# currentBaseBoard_v4.net
KiCad netlist of a schematic drawn in EAGLE
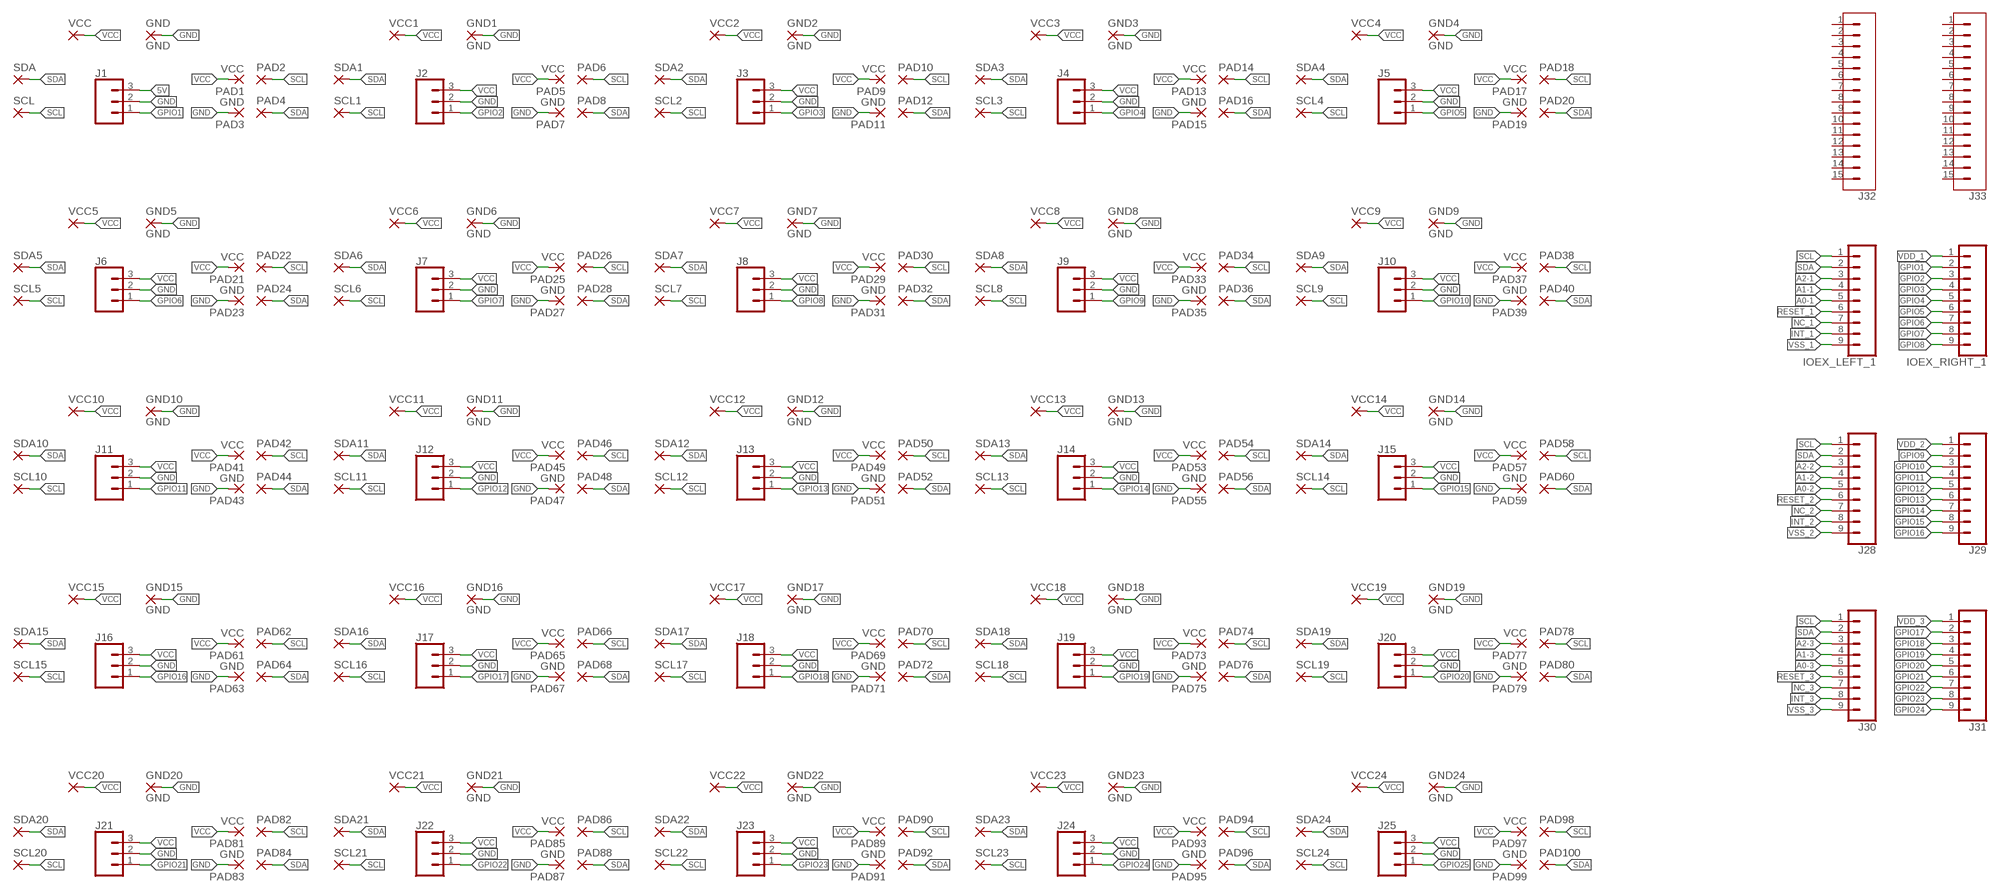
[diagram p0: schematic, sheet 1]

(export (version "E")
  (design (tool "Eeschema 10.0.6"))
  (components
    (comp (ref "GND")
      (value "GND")
      (footprint "eagle-import:2,15_1,0")
      (libsource (lib "eagle-import") (part "2,15/1,0"))
    )
    (comp (ref "GND1")
      (value "GND")
      (footprint "eagle-import:2,15_1,0")
      (libsource (lib "eagle-import") (part "2,15/1,0"))
    )
    (comp (ref "GND2")
      (value "GND")
      (footprint "eagle-import:2,15_1,0")
      (libsource (lib "eagle-import") (part "2,15/1,0"))
    )
    (comp (ref "GND3")
      (value "GND")
      (footprint "eagle-import:2,15_1,0")
      (libsource (lib "eagle-import") (part "2,15/1,0"))
    )
    (comp (ref "GND4")
      (value "GND")
      (footprint "eagle-import:2,15_1,0")
      (libsource (lib "eagle-import") (part "2,15/1,0"))
    )
    (comp (ref "GND5")
      (value "GND")
      (footprint "eagle-import:2,15_1,0")
      (libsource (lib "eagle-import") (part "2,15/1,0"))
    )
    (comp (ref "GND6")
      (value "GND")
      (footprint "eagle-import:2,15_1,0")
      (libsource (lib "eagle-import") (part "2,15/1,0"))
    )
    (comp (ref "GND7")
      (value "GND")
      (footprint "eagle-import:2,15_1,0")
      (libsource (lib "eagle-import") (part "2,15/1,0"))
    )
    (comp (ref "GND8")
      (value "GND")
      (footprint "eagle-import:2,15_1,0")
      (libsource (lib "eagle-import") (part "2,15/1,0"))
    )
    (comp (ref "GND9")
      (value "GND")
      (footprint "eagle-import:2,15_1,0")
      (libsource (lib "eagle-import") (part "2,15/1,0"))
    )
    (comp (ref "GND10")
      (value "GND")
      (footprint "eagle-import:2,15_1,0")
      (libsource (lib "eagle-import") (part "2,15/1,0"))
    )
    (comp (ref "GND11")
      (value "GND")
      (footprint "eagle-import:2,15_1,0")
      (libsource (lib "eagle-import") (part "2,15/1,0"))
    )
    (comp (ref "GND12")
      (value "GND")
      (footprint "eagle-import:2,15_1,0")
      (libsource (lib "eagle-import") (part "2,15/1,0"))
    )
    (comp (ref "GND13")
      (value "GND")
      (footprint "eagle-import:2,15_1,0")
      (libsource (lib "eagle-import") (part "2,15/1,0"))
    )
    (comp (ref "GND14")
      (value "GND")
      (footprint "eagle-import:2,15_1,0")
      (libsource (lib "eagle-import") (part "2,15/1,0"))
    )
    (comp (ref "GND15")
      (value "GND")
      (footprint "eagle-import:2,15_1,0")
      (libsource (lib "eagle-import") (part "2,15/1,0"))
    )
    (comp (ref "GND16")
      (value "GND")
      (footprint "eagle-import:2,15_1,0")
      (libsource (lib "eagle-import") (part "2,15/1,0"))
    )
    (comp (ref "GND17")
      (value "GND")
      (footprint "eagle-import:2,15_1,0")
      (libsource (lib "eagle-import") (part "2,15/1,0"))
    )
    (comp (ref "GND18")
      (value "GND")
      (footprint "eagle-import:2,15_1,0")
      (libsource (lib "eagle-import") (part "2,15/1,0"))
    )
    (comp (ref "GND19")
      (value "GND")
      (footprint "eagle-import:2,15_1,0")
      (libsource (lib "eagle-import") (part "2,15/1,0"))
    )
    (comp (ref "GND20")
      (value "GND")
      (footprint "eagle-import:2,15_1,0")
      (libsource (lib "eagle-import") (part "2,15/1,0"))
    )
    (comp (ref "GND21")
      (value "GND")
      (footprint "eagle-import:2,15_1,0")
      (libsource (lib "eagle-import") (part "2,15/1,0"))
    )
    (comp (ref "GND22")
      (value "GND")
      (footprint "eagle-import:2,15_1,0")
      (libsource (lib "eagle-import") (part "2,15/1,0"))
    )
    (comp (ref "GND23")
      (value "GND")
      (footprint "eagle-import:2,15_1,0")
      (libsource (lib "eagle-import") (part "2,15/1,0"))
    )
    (comp (ref "GND24")
      (value "GND")
      (footprint "eagle-import:2,15_1,0")
      (libsource (lib "eagle-import") (part "2,15/1,0"))
    )
    (comp (ref "IOEX_LEFT_1")
      (value "CONN_09")
      (footprint "eagle-import:1X09")
      (libsource (lib "eagle-import") (part "CONN_09"))
    )
    (comp (ref "IOEX_RIGHT_1")
      (value "CONN_09")
      (footprint "eagle-import:1X09")
      (libsource (lib "eagle-import") (part "CONN_09"))
    )
    (comp (ref "J1")
      (value "CONN_03")
      (footprint "eagle-import:1X03")
      (libsource (lib "eagle-import") (part "CONN_03"))
    )
    (comp (ref "J2")
      (value "CONN_03")
      (footprint "eagle-import:1X03")
      (libsource (lib "eagle-import") (part "CONN_03"))
    )
    (comp (ref "J3")
      (value "CONN_03")
      (footprint "eagle-import:1X03")
      (libsource (lib "eagle-import") (part "CONN_03"))
    )
    (comp (ref "J4")
      (value "CONN_03")
      (footprint "eagle-import:1X03")
      (libsource (lib "eagle-import") (part "CONN_03"))
    )
    (comp (ref "J5")
      (value "CONN_03")
      (footprint "eagle-import:1X03")
      (libsource (lib "eagle-import") (part "CONN_03"))
    )
    (comp (ref "J6")
      (value "CONN_03")
      (footprint "eagle-import:1X03")
      (libsource (lib "eagle-import") (part "CONN_03"))
    )
    (comp (ref "J7")
      (value "CONN_03")
      (footprint "eagle-import:1X03")
      (libsource (lib "eagle-import") (part "CONN_03"))
    )
    (comp (ref "J8")
      (value "CONN_03")
      (footprint "eagle-import:1X03")
      (libsource (lib "eagle-import") (part "CONN_03"))
    )
    (comp (ref "J9")
      (value "CONN_03")
      (footprint "eagle-import:1X03")
      (libsource (lib "eagle-import") (part "CONN_03"))
    )
    (comp (ref "J10")
      (value "CONN_03")
      (footprint "eagle-import:1X03")
      (libsource (lib "eagle-import") (part "CONN_03"))
    )
    (comp (ref "J11")
      (value "CONN_03")
      (footprint "eagle-import:1X03")
      (libsource (lib "eagle-import") (part "CONN_03"))
    )
    (comp (ref "J12")
      (value "CONN_03")
      (footprint "eagle-import:1X03")
      (libsource (lib "eagle-import") (part "CONN_03"))
    )
    (comp (ref "J13")
      (value "CONN_03")
      (footprint "eagle-import:1X03")
      (libsource (lib "eagle-import") (part "CONN_03"))
    )
    (comp (ref "J14")
      (value "CONN_03")
      (footprint "eagle-import:1X03")
      (libsource (lib "eagle-import") (part "CONN_03"))
    )
    (comp (ref "J15")
      (value "CONN_03")
      (footprint "eagle-import:1X03")
      (libsource (lib "eagle-import") (part "CONN_03"))
    )
    (comp (ref "J16")
      (value "CONN_03")
      (footprint "eagle-import:1X03")
      (libsource (lib "eagle-import") (part "CONN_03"))
    )
    (comp (ref "J17")
      (value "CONN_03")
      (footprint "eagle-import:1X03")
      (libsource (lib "eagle-import") (part "CONN_03"))
    )
    (comp (ref "J18")
      (value "CONN_03")
      (footprint "eagle-import:1X03")
      (libsource (lib "eagle-import") (part "CONN_03"))
    )
    (comp (ref "J19")
      (value "CONN_03")
      (footprint "eagle-import:1X03")
      (libsource (lib "eagle-import") (part "CONN_03"))
    )
    (comp (ref "J20")
      (value "CONN_03")
      (footprint "eagle-import:1X03")
      (libsource (lib "eagle-import") (part "CONN_03"))
    )
    (comp (ref "J21")
      (value "CONN_03")
      (footprint "eagle-import:1X03")
      (libsource (lib "eagle-import") (part "CONN_03"))
    )
    (comp (ref "J22")
      (value "CONN_03")
      (footprint "eagle-import:1X03")
      (libsource (lib "eagle-import") (part "CONN_03"))
    )
    (comp (ref "J23")
      (value "CONN_03")
      (footprint "eagle-import:1X03")
      (libsource (lib "eagle-import") (part "CONN_03"))
    )
    (comp (ref "J24")
      (value "CONN_03")
      (footprint "eagle-import:1X03")
      (libsource (lib "eagle-import") (part "CONN_03"))
    )
    (comp (ref "J25")
      (value "CONN_03")
      (footprint "eagle-import:1X03")
      (libsource (lib "eagle-import") (part "CONN_03"))
    )
    (comp (ref "J28")
      (value "CONN_09")
      (footprint "eagle-import:1X09")
      (libsource (lib "eagle-import") (part "CONN_09"))
    )
    (comp (ref "J29")
      (value "CONN_09")
      (footprint "eagle-import:1X09")
      (libsource (lib "eagle-import") (part "CONN_09"))
    )
    (comp (ref "J30")
      (value "CONN_09")
      (footprint "eagle-import:1X09")
      (libsource (lib "eagle-import") (part "CONN_09"))
    )
    (comp (ref "J31")
      (value "CONN_09")
      (footprint "eagle-import:1X09")
      (libsource (lib "eagle-import") (part "CONN_09"))
    )
    (comp (ref "J32")
      (value "CONN_06SMD_MALE")
      (footprint "eagle-import:1X15_SMD_MALE")
      (libsource (lib "eagle-import") (part "CONN_06SMD_MALE"))
    )
    (comp (ref "J33")
      (value "CONN_06SMD_MALE")
      (footprint "eagle-import:1X15_SMD_MALE")
      (libsource (lib "eagle-import") (part "CONN_06SMD_MALE"))
    )
    (comp (ref "PAD1")
      (value "VCC")
      (footprint "eagle-import:2,15_1,0")
      (libsource (lib "eagle-import") (part "2,15/1,0"))
    )
    (comp (ref "PAD2")
      (value "2,15/1,0")
      (footprint "eagle-import:2,15_1,0")
      (libsource (lib "eagle-import") (part "2,15/1,0"))
    )
    (comp (ref "PAD3")
      (value "GND")
      (footprint "eagle-import:2,15_1,0")
      (libsource (lib "eagle-import") (part "2,15/1,0"))
    )
    (comp (ref "PAD4")
      (value "2,15/1,0")
      (footprint "eagle-import:2,15_1,0")
      (libsource (lib "eagle-import") (part "2,15/1,0"))
    )
    (comp (ref "PAD5")
      (value "VCC")
      (footprint "eagle-import:2,15_1,0")
      (libsource (lib "eagle-import") (part "2,15/1,0"))
    )
    (comp (ref "PAD6")
      (value "2,15/1,0")
      (footprint "eagle-import:2,15_1,0")
      (libsource (lib "eagle-import") (part "2,15/1,0"))
    )
    (comp (ref "PAD7")
      (value "GND")
      (footprint "eagle-import:2,15_1,0")
      (libsource (lib "eagle-import") (part "2,15/1,0"))
    )
    (comp (ref "PAD8")
      (value "2,15/1,0")
      (footprint "eagle-import:2,15_1,0")
      (libsource (lib "eagle-import") (part "2,15/1,0"))
    )
    (comp (ref "PAD9")
      (value "VCC")
      (footprint "eagle-import:2,15_1,0")
      (libsource (lib "eagle-import") (part "2,15/1,0"))
    )
    (comp (ref "PAD10")
      (value "2,15/1,0")
      (footprint "eagle-import:2,15_1,0")
      (libsource (lib "eagle-import") (part "2,15/1,0"))
    )
    (comp (ref "PAD11")
      (value "GND")
      (footprint "eagle-import:2,15_1,0")
      (libsource (lib "eagle-import") (part "2,15/1,0"))
    )
    (comp (ref "PAD12")
      (value "2,15/1,0")
      (footprint "eagle-import:2,15_1,0")
      (libsource (lib "eagle-import") (part "2,15/1,0"))
    )
    (comp (ref "PAD13")
      (value "VCC")
      (footprint "eagle-import:2,15_1,0")
      (libsource (lib "eagle-import") (part "2,15/1,0"))
    )
    (comp (ref "PAD14")
      (value "2,15/1,0")
      (footprint "eagle-import:2,15_1,0")
      (libsource (lib "eagle-import") (part "2,15/1,0"))
    )
    (comp (ref "PAD15")
      (value "GND")
      (footprint "eagle-import:2,15_1,0")
      (libsource (lib "eagle-import") (part "2,15/1,0"))
    )
    (comp (ref "PAD16")
      (value "2,15/1,0")
      (footprint "eagle-import:2,15_1,0")
      (libsource (lib "eagle-import") (part "2,15/1,0"))
    )
    (comp (ref "PAD17")
      (value "VCC")
      (footprint "eagle-import:2,15_1,0")
      (libsource (lib "eagle-import") (part "2,15/1,0"))
    )
    (comp (ref "PAD18")
      (value "2,15/1,0")
      (footprint "eagle-import:2,15_1,0")
      (libsource (lib "eagle-import") (part "2,15/1,0"))
    )
    (comp (ref "PAD19")
      (value "GND")
      (footprint "eagle-import:2,15_1,0")
      (libsource (lib "eagle-import") (part "2,15/1,0"))
    )
    (comp (ref "PAD20")
      (value "2,15/1,0")
      (footprint "eagle-import:2,15_1,0")
      (libsource (lib "eagle-import") (part "2,15/1,0"))
    )
    (comp (ref "PAD21")
      (value "VCC")
      (footprint "eagle-import:2,15_1,0")
      (libsource (lib "eagle-import") (part "2,15/1,0"))
    )
    (comp (ref "PAD22")
      (value "2,15/1,0")
      (footprint "eagle-import:2,15_1,0")
      (libsource (lib "eagle-import") (part "2,15/1,0"))
    )
    (comp (ref "PAD23")
      (value "GND")
      (footprint "eagle-import:2,15_1,0")
      (libsource (lib "eagle-import") (part "2,15/1,0"))
    )
    (comp (ref "PAD24")
      (value "2,15/1,0")
      (footprint "eagle-import:2,15_1,0")
      (libsource (lib "eagle-import") (part "2,15/1,0"))
    )
    (comp (ref "PAD25")
      (value "VCC")
      (footprint "eagle-import:2,15_1,0")
      (libsource (lib "eagle-import") (part "2,15/1,0"))
    )
    (comp (ref "PAD26")
      (value "2,15/1,0")
      (footprint "eagle-import:2,15_1,0")
      (libsource (lib "eagle-import") (part "2,15/1,0"))
    )
    (comp (ref "PAD27")
      (value "GND")
      (footprint "eagle-import:2,15_1,0")
      (libsource (lib "eagle-import") (part "2,15/1,0"))
    )
    (comp (ref "PAD28")
      (value "2,15/1,0")
      (footprint "eagle-import:2,15_1,0")
      (libsource (lib "eagle-import") (part "2,15/1,0"))
    )
    (comp (ref "PAD29")
      (value "VCC")
      (footprint "eagle-import:2,15_1,0")
      (libsource (lib "eagle-import") (part "2,15/1,0"))
    )
    (comp (ref "PAD30")
      (value "2,15/1,0")
      (footprint "eagle-import:2,15_1,0")
      (libsource (lib "eagle-import") (part "2,15/1,0"))
    )
    (comp (ref "PAD31")
      (value "GND")
      (footprint "eagle-import:2,15_1,0")
      (libsource (lib "eagle-import") (part "2,15/1,0"))
    )
    (comp (ref "PAD32")
      (value "2,15/1,0")
      (footprint "eagle-import:2,15_1,0")
      (libsource (lib "eagle-import") (part "2,15/1,0"))
    )
    (comp (ref "PAD33")
      (value "VCC")
      (footprint "eagle-import:2,15_1,0")
      (libsource (lib "eagle-import") (part "2,15/1,0"))
    )
    (comp (ref "PAD34")
      (value "2,15/1,0")
      (footprint "eagle-import:2,15_1,0")
      (libsource (lib "eagle-import") (part "2,15/1,0"))
    )
    (comp (ref "PAD35")
      (value "GND")
      (footprint "eagle-import:2,15_1,0")
      (libsource (lib "eagle-import") (part "2,15/1,0"))
    )
    (comp (ref "PAD36")
      (value "2,15/1,0")
      (footprint "eagle-import:2,15_1,0")
      (libsource (lib "eagle-import") (part "2,15/1,0"))
    )
    (comp (ref "PAD37")
      (value "VCC")
      (footprint "eagle-import:2,15_1,0")
      (libsource (lib "eagle-import") (part "2,15/1,0"))
    )
    (comp (ref "PAD38")
      (value "2,15/1,0")
      (footprint "eagle-import:2,15_1,0")
      (libsource (lib "eagle-import") (part "2,15/1,0"))
    )
    (comp (ref "PAD39")
      (value "GND")
      (footprint "eagle-import:2,15_1,0")
      (libsource (lib "eagle-import") (part "2,15/1,0"))
    )
    (comp (ref "PAD40")
      (value "2,15/1,0")
      (footprint "eagle-import:2,15_1,0")
      (libsource (lib "eagle-import") (part "2,15/1,0"))
    )
    (comp (ref "PAD41")
      (value "VCC")
      (footprint "eagle-import:2,15_1,0")
      (libsource (lib "eagle-import") (part "2,15/1,0"))
    )
    (comp (ref "PAD42")
      (value "2,15/1,0")
      (footprint "eagle-import:2,15_1,0")
      (libsource (lib "eagle-import") (part "2,15/1,0"))
    )
    (comp (ref "PAD43")
      (value "GND")
      (footprint "eagle-import:2,15_1,0")
      (libsource (lib "eagle-import") (part "2,15/1,0"))
    )
    (comp (ref "PAD44")
      (value "2,15/1,0")
      (footprint "eagle-import:2,15_1,0")
      (libsource (lib "eagle-import") (part "2,15/1,0"))
    )
    (comp (ref "PAD45")
      (value "VCC")
      (footprint "eagle-import:2,15_1,0")
      (libsource (lib "eagle-import") (part "2,15/1,0"))
    )
    (comp (ref "PAD46")
      (value "2,15/1,0")
      (footprint "eagle-import:2,15_1,0")
      (libsource (lib "eagle-import") (part "2,15/1,0"))
    )
    (comp (ref "PAD47")
      (value "GND")
      (footprint "eagle-import:2,15_1,0")
      (libsource (lib "eagle-import") (part "2,15/1,0"))
    )
    (comp (ref "PAD48")
      (value "2,15/1,0")
      (footprint "eagle-import:2,15_1,0")
      (libsource (lib "eagle-import") (part "2,15/1,0"))
    )
    (comp (ref "PAD49")
      (value "VCC")
      (footprint "eagle-import:2,15_1,0")
      (libsource (lib "eagle-import") (part "2,15/1,0"))
    )
    (comp (ref "PAD50")
      (value "2,15/1,0")
      (footprint "eagle-import:2,15_1,0")
      (libsource (lib "eagle-import") (part "2,15/1,0"))
    )
    (comp (ref "PAD51")
      (value "GND")
      (footprint "eagle-import:2,15_1,0")
      (libsource (lib "eagle-import") (part "2,15/1,0"))
    )
    (comp (ref "PAD52")
      (value "2,15/1,0")
      (footprint "eagle-import:2,15_1,0")
      (libsource (lib "eagle-import") (part "2,15/1,0"))
    )
    (comp (ref "PAD53")
      (value "VCC")
      (footprint "eagle-import:2,15_1,0")
      (libsource (lib "eagle-import") (part "2,15/1,0"))
    )
    (comp (ref "PAD54")
      (value "2,15/1,0")
      (footprint "eagle-import:2,15_1,0")
      (libsource (lib "eagle-import") (part "2,15/1,0"))
    )
    (comp (ref "PAD55")
      (value "GND")
      (footprint "eagle-import:2,15_1,0")
      (libsource (lib "eagle-import") (part "2,15/1,0"))
    )
    (comp (ref "PAD56")
      (value "2,15/1,0")
      (footprint "eagle-import:2,15_1,0")
      (libsource (lib "eagle-import") (part "2,15/1,0"))
    )
    (comp (ref "PAD57")
      (value "VCC")
      (footprint "eagle-import:2,15_1,0")
      (libsource (lib "eagle-import") (part "2,15/1,0"))
    )
    (comp (ref "PAD58")
      (value "2,15/1,0")
      (footprint "eagle-import:2,15_1,0")
      (libsource (lib "eagle-import") (part "2,15/1,0"))
    )
    (comp (ref "PAD59")
      (value "GND")
      (footprint "eagle-import:2,15_1,0")
      (libsource (lib "eagle-import") (part "2,15/1,0"))
    )
    (comp (ref "PAD60")
      (value "2,15/1,0")
      (footprint "eagle-import:2,15_1,0")
      (libsource (lib "eagle-import") (part "2,15/1,0"))
    )
    (comp (ref "PAD61")
      (value "VCC")
      (footprint "eagle-import:2,15_1,0")
      (libsource (lib "eagle-import") (part "2,15/1,0"))
    )
    (comp (ref "PAD62")
      (value "2,15/1,0")
      (footprint "eagle-import:2,15_1,0")
      (libsource (lib "eagle-import") (part "2,15/1,0"))
    )
    (comp (ref "PAD63")
      (value "GND")
      (footprint "eagle-import:2,15_1,0")
      (libsource (lib "eagle-import") (part "2,15/1,0"))
    )
    (comp (ref "PAD64")
      (value "2,15/1,0")
      (footprint "eagle-import:2,15_1,0")
      (libsource (lib "eagle-import") (part "2,15/1,0"))
    )
    (comp (ref "PAD65")
      (value "VCC")
      (footprint "eagle-import:2,15_1,0")
      (libsource (lib "eagle-import") (part "2,15/1,0"))
    )
    (comp (ref "PAD66")
      (value "2,15/1,0")
      (footprint "eagle-import:2,15_1,0")
      (libsource (lib "eagle-import") (part "2,15/1,0"))
    )
    (comp (ref "PAD67")
      (value "GND")
      (footprint "eagle-import:2,15_1,0")
      (libsource (lib "eagle-import") (part "2,15/1,0"))
    )
    (comp (ref "PAD68")
      (value "2,15/1,0")
      (footprint "eagle-import:2,15_1,0")
      (libsource (lib "eagle-import") (part "2,15/1,0"))
    )
    (comp (ref "PAD69")
      (value "VCC")
      (footprint "eagle-import:2,15_1,0")
      (libsource (lib "eagle-import") (part "2,15/1,0"))
    )
    (comp (ref "PAD70")
      (value "2,15/1,0")
      (footprint "eagle-import:2,15_1,0")
      (libsource (lib "eagle-import") (part "2,15/1,0"))
    )
    (comp (ref "PAD71")
      (value "GND")
      (footprint "eagle-import:2,15_1,0")
      (libsource (lib "eagle-import") (part "2,15/1,0"))
    )
    (comp (ref "PAD72")
      (value "2,15/1,0")
      (footprint "eagle-import:2,15_1,0")
      (libsource (lib "eagle-import") (part "2,15/1,0"))
    )
    (comp (ref "PAD73")
      (value "VCC")
      (footprint "eagle-import:2,15_1,0")
      (libsource (lib "eagle-import") (part "2,15/1,0"))
    )
    (comp (ref "PAD74")
      (value "2,15/1,0")
      (footprint "eagle-import:2,15_1,0")
      (libsource (lib "eagle-import") (part "2,15/1,0"))
    )
    (comp (ref "PAD75")
      (value "GND")
      (footprint "eagle-import:2,15_1,0")
      (libsource (lib "eagle-import") (part "2,15/1,0"))
    )
    (comp (ref "PAD76")
      (value "2,15/1,0")
      (footprint "eagle-import:2,15_1,0")
      (libsource (lib "eagle-import") (part "2,15/1,0"))
    )
    (comp (ref "PAD77")
      (value "VCC")
      (footprint "eagle-import:2,15_1,0")
      (libsource (lib "eagle-import") (part "2,15/1,0"))
    )
    (comp (ref "PAD78")
      (value "2,15/1,0")
      (footprint "eagle-import:2,15_1,0")
      (libsource (lib "eagle-import") (part "2,15/1,0"))
    )
    (comp (ref "PAD79")
      (value "GND")
      (footprint "eagle-import:2,15_1,0")
      (libsource (lib "eagle-import") (part "2,15/1,0"))
    )
    (comp (ref "PAD80")
      (value "2,15/1,0")
      (footprint "eagle-import:2,15_1,0")
      (libsource (lib "eagle-import") (part "2,15/1,0"))
    )
    (comp (ref "PAD81")
      (value "VCC")
      (footprint "eagle-import:2,15_1,0")
      (libsource (lib "eagle-import") (part "2,15/1,0"))
    )
    (comp (ref "PAD82")
      (value "2,15/1,0")
      (footprint "eagle-import:2,15_1,0")
      (libsource (lib "eagle-import") (part "2,15/1,0"))
    )
    (comp (ref "PAD83")
      (value "GND")
      (footprint "eagle-import:2,15_1,0")
      (libsource (lib "eagle-import") (part "2,15/1,0"))
    )
    (comp (ref "PAD84")
      (value "2,15/1,0")
      (footprint "eagle-import:2,15_1,0")
      (libsource (lib "eagle-import") (part "2,15/1,0"))
    )
    (comp (ref "PAD85")
      (value "VCC")
      (footprint "eagle-import:2,15_1,0")
      (libsource (lib "eagle-import") (part "2,15/1,0"))
    )
    (comp (ref "PAD86")
      (value "2,15/1,0")
      (footprint "eagle-import:2,15_1,0")
      (libsource (lib "eagle-import") (part "2,15/1,0"))
    )
    (comp (ref "PAD87")
      (value "GND")
      (footprint "eagle-import:2,15_1,0")
      (libsource (lib "eagle-import") (part "2,15/1,0"))
    )
    (comp (ref "PAD88")
      (value "2,15/1,0")
      (footprint "eagle-import:2,15_1,0")
      (libsource (lib "eagle-import") (part "2,15/1,0"))
    )
    (comp (ref "PAD89")
      (value "VCC")
      (footprint "eagle-import:2,15_1,0")
      (libsource (lib "eagle-import") (part "2,15/1,0"))
    )
    (comp (ref "PAD90")
      (value "2,15/1,0")
      (footprint "eagle-import:2,15_1,0")
      (libsource (lib "eagle-import") (part "2,15/1,0"))
    )
    (comp (ref "PAD91")
      (value "GND")
      (footprint "eagle-import:2,15_1,0")
      (libsource (lib "eagle-import") (part "2,15/1,0"))
    )
    (comp (ref "PAD92")
      (value "2,15/1,0")
      (footprint "eagle-import:2,15_1,0")
      (libsource (lib "eagle-import") (part "2,15/1,0"))
    )
    (comp (ref "PAD93")
      (value "VCC")
      (footprint "eagle-import:2,15_1,0")
      (libsource (lib "eagle-import") (part "2,15/1,0"))
    )
    (comp (ref "PAD94")
      (value "2,15/1,0")
      (footprint "eagle-import:2,15_1,0")
      (libsource (lib "eagle-import") (part "2,15/1,0"))
    )
    (comp (ref "PAD95")
      (value "GND")
      (footprint "eagle-import:2,15_1,0")
      (libsource (lib "eagle-import") (part "2,15/1,0"))
    )
    (comp (ref "PAD96")
      (value "2,15/1,0")
      (footprint "eagle-import:2,15_1,0")
      (libsource (lib "eagle-import") (part "2,15/1,0"))
    )
    (comp (ref "PAD97")
      (value "VCC")
      (footprint "eagle-import:2,15_1,0")
      (libsource (lib "eagle-import") (part "2,15/1,0"))
    )
    (comp (ref "PAD98")
      (value "2,15/1,0")
      (footprint "eagle-import:2,15_1,0")
      (libsource (lib "eagle-import") (part "2,15/1,0"))
    )
    (comp (ref "PAD99")
      (value "GND")
      (footprint "eagle-import:2,15_1,0")
      (libsource (lib "eagle-import") (part "2,15/1,0"))
    )
    (comp (ref "PAD100")
      (value "2,15/1,0")
      (footprint "eagle-import:2,15_1,0")
      (libsource (lib "eagle-import") (part "2,15/1,0"))
    )
    (comp (ref "SCL")
      (value "2,15/1,0")
      (footprint "eagle-import:2,15_1,0")
      (libsource (lib "eagle-import") (part "2,15/1,0"))
    )
    (comp (ref "SCL1")
      (value "2,15/1,0")
      (footprint "eagle-import:2,15_1,0")
      (libsource (lib "eagle-import") (part "2,15/1,0"))
    )
    (comp (ref "SCL2")
      (value "2,15/1,0")
      (footprint "eagle-import:2,15_1,0")
      (libsource (lib "eagle-import") (part "2,15/1,0"))
    )
    (comp (ref "SCL3")
      (value "2,15/1,0")
      (footprint "eagle-import:2,15_1,0")
      (libsource (lib "eagle-import") (part "2,15/1,0"))
    )
    (comp (ref "SCL4")
      (value "2,15/1,0")
      (footprint "eagle-import:2,15_1,0")
      (libsource (lib "eagle-import") (part "2,15/1,0"))
    )
    (comp (ref "SCL5")
      (value "2,15/1,0")
      (footprint "eagle-import:2,15_1,0")
      (libsource (lib "eagle-import") (part "2,15/1,0"))
    )
    (comp (ref "SCL6")
      (value "2,15/1,0")
      (footprint "eagle-import:2,15_1,0")
      (libsource (lib "eagle-import") (part "2,15/1,0"))
    )
    (comp (ref "SCL7")
      (value "2,15/1,0")
      (footprint "eagle-import:2,15_1,0")
      (libsource (lib "eagle-import") (part "2,15/1,0"))
    )
    (comp (ref "SCL8")
      (value "2,15/1,0")
      (footprint "eagle-import:2,15_1,0")
      (libsource (lib "eagle-import") (part "2,15/1,0"))
    )
    (comp (ref "SCL9")
      (value "2,15/1,0")
      (footprint "eagle-import:2,15_1,0")
      (libsource (lib "eagle-import") (part "2,15/1,0"))
    )
    (comp (ref "SCL10")
      (value "2,15/1,0")
      (footprint "eagle-import:2,15_1,0")
      (libsource (lib "eagle-import") (part "2,15/1,0"))
    )
    (comp (ref "SCL11")
      (value "2,15/1,0")
      (footprint "eagle-import:2,15_1,0")
      (libsource (lib "eagle-import") (part "2,15/1,0"))
    )
    (comp (ref "SCL12")
      (value "2,15/1,0")
      (footprint "eagle-import:2,15_1,0")
      (libsource (lib "eagle-import") (part "2,15/1,0"))
    )
    (comp (ref "SCL13")
      (value "2,15/1,0")
      (footprint "eagle-import:2,15_1,0")
      (libsource (lib "eagle-import") (part "2,15/1,0"))
    )
    (comp (ref "SCL14")
      (value "2,15/1,0")
      (footprint "eagle-import:2,15_1,0")
      (libsource (lib "eagle-import") (part "2,15/1,0"))
    )
    (comp (ref "SCL15")
      (value "2,15/1,0")
      (footprint "eagle-import:2,15_1,0")
      (libsource (lib "eagle-import") (part "2,15/1,0"))
    )
    (comp (ref "SCL16")
      (value "2,15/1,0")
      (footprint "eagle-import:2,15_1,0")
      (libsource (lib "eagle-import") (part "2,15/1,0"))
    )
    (comp (ref "SCL17")
      (value "2,15/1,0")
      (footprint "eagle-import:2,15_1,0")
      (libsource (lib "eagle-import") (part "2,15/1,0"))
    )
    (comp (ref "SCL18")
      (value "2,15/1,0")
      (footprint "eagle-import:2,15_1,0")
      (libsource (lib "eagle-import") (part "2,15/1,0"))
    )
    (comp (ref "SCL19")
      (value "2,15/1,0")
      (footprint "eagle-import:2,15_1,0")
      (libsource (lib "eagle-import") (part "2,15/1,0"))
    )
    (comp (ref "SCL20")
      (value "2,15/1,0")
      (footprint "eagle-import:2,15_1,0")
      (libsource (lib "eagle-import") (part "2,15/1,0"))
    )
    (comp (ref "SCL21")
      (value "2,15/1,0")
      (footprint "eagle-import:2,15_1,0")
      (libsource (lib "eagle-import") (part "2,15/1,0"))
    )
    (comp (ref "SCL22")
      (value "2,15/1,0")
      (footprint "eagle-import:2,15_1,0")
      (libsource (lib "eagle-import") (part "2,15/1,0"))
    )
    (comp (ref "SCL23")
      (value "2,15/1,0")
      (footprint "eagle-import:2,15_1,0")
      (libsource (lib "eagle-import") (part "2,15/1,0"))
    )
    (comp (ref "SCL24")
      (value "2,15/1,0")
      (footprint "eagle-import:2,15_1,0")
      (libsource (lib "eagle-import") (part "2,15/1,0"))
    )
    (comp (ref "SDA")
      (value "2,15/1,0")
      (footprint "eagle-import:2,15_1,0")
      (libsource (lib "eagle-import") (part "2,15/1,0"))
    )
    (comp (ref "SDA1")
      (value "2,15/1,0")
      (footprint "eagle-import:2,15_1,0")
      (libsource (lib "eagle-import") (part "2,15/1,0"))
    )
    (comp (ref "SDA2")
      (value "2,15/1,0")
      (footprint "eagle-import:2,15_1,0")
      (libsource (lib "eagle-import") (part "2,15/1,0"))
    )
    (comp (ref "SDA3")
      (value "2,15/1,0")
      (footprint "eagle-import:2,15_1,0")
      (libsource (lib "eagle-import") (part "2,15/1,0"))
    )
    (comp (ref "SDA4")
      (value "2,15/1,0")
      (footprint "eagle-import:2,15_1,0")
      (libsource (lib "eagle-import") (part "2,15/1,0"))
    )
    (comp (ref "SDA5")
      (value "2,15/1,0")
      (footprint "eagle-import:2,15_1,0")
      (libsource (lib "eagle-import") (part "2,15/1,0"))
    )
    (comp (ref "SDA6")
      (value "2,15/1,0")
      (footprint "eagle-import:2,15_1,0")
      (libsource (lib "eagle-import") (part "2,15/1,0"))
    )
    (comp (ref "SDA7")
      (value "2,15/1,0")
      (footprint "eagle-import:2,15_1,0")
      (libsource (lib "eagle-import") (part "2,15/1,0"))
    )
    (comp (ref "SDA8")
      (value "2,15/1,0")
      (footprint "eagle-import:2,15_1,0")
      (libsource (lib "eagle-import") (part "2,15/1,0"))
    )
    (comp (ref "SDA9")
      (value "2,15/1,0")
      (footprint "eagle-import:2,15_1,0")
      (libsource (lib "eagle-import") (part "2,15/1,0"))
    )
    (comp (ref "SDA10")
      (value "2,15/1,0")
      (footprint "eagle-import:2,15_1,0")
      (libsource (lib "eagle-import") (part "2,15/1,0"))
    )
    (comp (ref "SDA11")
      (value "2,15/1,0")
      (footprint "eagle-import:2,15_1,0")
      (libsource (lib "eagle-import") (part "2,15/1,0"))
    )
    (comp (ref "SDA12")
      (value "2,15/1,0")
      (footprint "eagle-import:2,15_1,0")
      (libsource (lib "eagle-import") (part "2,15/1,0"))
    )
    (comp (ref "SDA13")
      (value "2,15/1,0")
      (footprint "eagle-import:2,15_1,0")
      (libsource (lib "eagle-import") (part "2,15/1,0"))
    )
    (comp (ref "SDA14")
      (value "2,15/1,0")
      (footprint "eagle-import:2,15_1,0")
      (libsource (lib "eagle-import") (part "2,15/1,0"))
    )
    (comp (ref "SDA15")
      (value "2,15/1,0")
      (footprint "eagle-import:2,15_1,0")
      (libsource (lib "eagle-import") (part "2,15/1,0"))
    )
    (comp (ref "SDA16")
      (value "2,15/1,0")
      (footprint "eagle-import:2,15_1,0")
      (libsource (lib "eagle-import") (part "2,15/1,0"))
    )
    (comp (ref "SDA17")
      (value "2,15/1,0")
      (footprint "eagle-import:2,15_1,0")
      (libsource (lib "eagle-import") (part "2,15/1,0"))
    )
    (comp (ref "SDA18")
      (value "2,15/1,0")
      (footprint "eagle-import:2,15_1,0")
      (libsource (lib "eagle-import") (part "2,15/1,0"))
    )
    (comp (ref "SDA19")
      (value "2,15/1,0")
      (footprint "eagle-import:2,15_1,0")
      (libsource (lib "eagle-import") (part "2,15/1,0"))
    )
    (comp (ref "SDA20")
      (value "2,15/1,0")
      (footprint "eagle-import:2,15_1,0")
      (libsource (lib "eagle-import") (part "2,15/1,0"))
    )
    (comp (ref "SDA21")
      (value "2,15/1,0")
      (footprint "eagle-import:2,15_1,0")
      (libsource (lib "eagle-import") (part "2,15/1,0"))
    )
    (comp (ref "SDA22")
      (value "2,15/1,0")
      (footprint "eagle-import:2,15_1,0")
      (libsource (lib "eagle-import") (part "2,15/1,0"))
    )
    (comp (ref "SDA23")
      (value "2,15/1,0")
      (footprint "eagle-import:2,15_1,0")
      (libsource (lib "eagle-import") (part "2,15/1,0"))
    )
    (comp (ref "SDA24")
      (value "2,15/1,0")
      (footprint "eagle-import:2,15_1,0")
      (libsource (lib "eagle-import") (part "2,15/1,0"))
    )
    (comp (ref "VCC")
      (value "2,15/1,0")
      (footprint "eagle-import:2,15_1,0")
      (libsource (lib "eagle-import") (part "2,15/1,0"))
    )
    (comp (ref "VCC1")
      (value "2,15/1,0")
      (footprint "eagle-import:2,15_1,0")
      (libsource (lib "eagle-import") (part "2,15/1,0"))
    )
    (comp (ref "VCC2")
      (value "2,15/1,0")
      (footprint "eagle-import:2,15_1,0")
      (libsource (lib "eagle-import") (part "2,15/1,0"))
    )
    (comp (ref "VCC3")
      (value "2,15/1,0")
      (footprint "eagle-import:2,15_1,0")
      (libsource (lib "eagle-import") (part "2,15/1,0"))
    )
    (comp (ref "VCC4")
      (value "2,15/1,0")
      (footprint "eagle-import:2,15_1,0")
      (libsource (lib "eagle-import") (part "2,15/1,0"))
    )
    (comp (ref "VCC5")
      (value "2,15/1,0")
      (footprint "eagle-import:2,15_1,0")
      (libsource (lib "eagle-import") (part "2,15/1,0"))
    )
    (comp (ref "VCC6")
      (value "2,15/1,0")
      (footprint "eagle-import:2,15_1,0")
      (libsource (lib "eagle-import") (part "2,15/1,0"))
    )
    (comp (ref "VCC7")
      (value "2,15/1,0")
      (footprint "eagle-import:2,15_1,0")
      (libsource (lib "eagle-import") (part "2,15/1,0"))
    )
    (comp (ref "VCC8")
      (value "2,15/1,0")
      (footprint "eagle-import:2,15_1,0")
      (libsource (lib "eagle-import") (part "2,15/1,0"))
    )
    (comp (ref "VCC9")
      (value "2,15/1,0")
      (footprint "eagle-import:2,15_1,0")
      (libsource (lib "eagle-import") (part "2,15/1,0"))
    )
    (comp (ref "VCC10")
      (value "2,15/1,0")
      (footprint "eagle-import:2,15_1,0")
      (libsource (lib "eagle-import") (part "2,15/1,0"))
    )
    (comp (ref "VCC11")
      (value "2,15/1,0")
      (footprint "eagle-import:2,15_1,0")
      (libsource (lib "eagle-import") (part "2,15/1,0"))
    )
    (comp (ref "VCC12")
      (value "2,15/1,0")
      (footprint "eagle-import:2,15_1,0")
      (libsource (lib "eagle-import") (part "2,15/1,0"))
    )
    (comp (ref "VCC13")
      (value "2,15/1,0")
      (footprint "eagle-import:2,15_1,0")
      (libsource (lib "eagle-import") (part "2,15/1,0"))
    )
    (comp (ref "VCC14")
      (value "2,15/1,0")
      (footprint "eagle-import:2,15_1,0")
      (libsource (lib "eagle-import") (part "2,15/1,0"))
    )
    (comp (ref "VCC15")
      (value "2,15/1,0")
      (footprint "eagle-import:2,15_1,0")
      (libsource (lib "eagle-import") (part "2,15/1,0"))
    )
    (comp (ref "VCC16")
      (value "2,15/1,0")
      (footprint "eagle-import:2,15_1,0")
      (libsource (lib "eagle-import") (part "2,15/1,0"))
    )
    (comp (ref "VCC17")
      (value "2,15/1,0")
      (footprint "eagle-import:2,15_1,0")
      (libsource (lib "eagle-import") (part "2,15/1,0"))
    )
    (comp (ref "VCC18")
      (value "2,15/1,0")
      (footprint "eagle-import:2,15_1,0")
      (libsource (lib "eagle-import") (part "2,15/1,0"))
    )
    (comp (ref "VCC19")
      (value "2,15/1,0")
      (footprint "eagle-import:2,15_1,0")
      (libsource (lib "eagle-import") (part "2,15/1,0"))
    )
    (comp (ref "VCC20")
      (value "2,15/1,0")
      (footprint "eagle-import:2,15_1,0")
      (libsource (lib "eagle-import") (part "2,15/1,0"))
    )
    (comp (ref "VCC21")
      (value "2,15/1,0")
      (footprint "eagle-import:2,15_1,0")
      (libsource (lib "eagle-import") (part "2,15/1,0"))
    )
    (comp (ref "VCC22")
      (value "2,15/1,0")
      (footprint "eagle-import:2,15_1,0")
      (libsource (lib "eagle-import") (part "2,15/1,0"))
    )
    (comp (ref "VCC23")
      (value "2,15/1,0")
      (footprint "eagle-import:2,15_1,0")
      (libsource (lib "eagle-import") (part "2,15/1,0"))
    )
    (comp (ref "VCC24")
      (value "2,15/1,0")
      (footprint "eagle-import:2,15_1,0")
      (libsource (lib "eagle-import") (part "2,15/1,0"))
    )
  )
  (nets
    (net (code "1") (name "5V") (class "Default")
      (node (ref "J1") (pin "3") (pinfunction "3_3") (pintype "passive"))
    )
    (net (code "2") (name "A0-1") (class "Default")
      (node (ref "IOEX_LEFT_1") (pin "5") (pinfunction "5_5") (pintype "passive"))
    )
    (net (code "3") (name "A0-2") (class "Default")
      (node (ref "J28") (pin "5") (pinfunction "5_5") (pintype "passive"))
    )
    (net (code "4") (name "A0-3") (class "Default")
      (node (ref "J30") (pin "5") (pinfunction "5_5") (pintype "passive"))
    )
    (net (code "5") (name "A1-1") (class "Default")
      (node (ref "IOEX_LEFT_1") (pin "4") (pinfunction "4_4") (pintype "passive"))
    )
    (net (code "6") (name "A1-2") (class "Default")
      (node (ref "J28") (pin "4") (pinfunction "4_4") (pintype "passive"))
    )
    (net (code "7") (name "A1-3") (class "Default")
      (node (ref "J30") (pin "4") (pinfunction "4_4") (pintype "passive"))
    )
    (net (code "8") (name "A2-1") (class "Default")
      (node (ref "IOEX_LEFT_1") (pin "3") (pinfunction "3_3") (pintype "passive"))
    )
    (net (code "9") (name "A2-2") (class "Default")
      (node (ref "J28") (pin "3") (pinfunction "3_3") (pintype "passive"))
    )
    (net (code "10") (name "A2-3") (class "Default")
      (node (ref "J30") (pin "3") (pinfunction "3_3") (pintype "passive"))
    )
    (net (code "11") (name "GND") (class "Default")
      (node (ref "GND") (pin "1") (pinfunction "P_1") (pintype "passive"))
      (node (ref "GND1") (pin "1") (pinfunction "P_1") (pintype "passive"))
      (node (ref "GND10") (pin "1") (pinfunction "P_1") (pintype "passive"))
      (node (ref "GND11") (pin "1") (pinfunction "P_1") (pintype "passive"))
      (node (ref "GND12") (pin "1") (pinfunction "P_1") (pintype "passive"))
      (node (ref "GND13") (pin "1") (pinfunction "P_1") (pintype "passive"))
      (node (ref "GND14") (pin "1") (pinfunction "P_1") (pintype "passive"))
      (node (ref "GND15") (pin "1") (pinfunction "P_1") (pintype "passive"))
      (node (ref "GND16") (pin "1") (pinfunction "P_1") (pintype "passive"))
      (node (ref "GND17") (pin "1") (pinfunction "P_1") (pintype "passive"))
      (node (ref "GND18") (pin "1") (pinfunction "P_1") (pintype "passive"))
      (node (ref "GND19") (pin "1") (pinfunction "P_1") (pintype "passive"))
      (node (ref "GND2") (pin "1") (pinfunction "P_1") (pintype "passive"))
      (node (ref "GND20") (pin "1") (pinfunction "P_1") (pintype "passive"))
      (node (ref "GND21") (pin "1") (pinfunction "P_1") (pintype "passive"))
      (node (ref "GND22") (pin "1") (pinfunction "P_1") (pintype "passive"))
      (node (ref "GND23") (pin "1") (pinfunction "P_1") (pintype "passive"))
      (node (ref "GND24") (pin "1") (pinfunction "P_1") (pintype "passive"))
      (node (ref "GND3") (pin "1") (pinfunction "P_1") (pintype "passive"))
      (node (ref "GND4") (pin "1") (pinfunction "P_1") (pintype "passive"))
      (node (ref "GND5") (pin "1") (pinfunction "P_1") (pintype "passive"))
      (node (ref "GND6") (pin "1") (pinfunction "P_1") (pintype "passive"))
      (node (ref "GND7") (pin "1") (pinfunction "P_1") (pintype "passive"))
      (node (ref "GND8") (pin "1") (pinfunction "P_1") (pintype "passive"))
      (node (ref "GND9") (pin "1") (pinfunction "P_1") (pintype "passive"))
      (node (ref "J1") (pin "2") (pinfunction "2_2") (pintype "passive"))
      (node (ref "J10") (pin "2") (pinfunction "2_2") (pintype "passive"))
      (node (ref "J11") (pin "2") (pinfunction "2_2") (pintype "passive"))
      (node (ref "J12") (pin "2") (pinfunction "2_2") (pintype "passive"))
      (node (ref "J13") (pin "2") (pinfunction "2_2") (pintype "passive"))
      (node (ref "J14") (pin "2") (pinfunction "2_2") (pintype "passive"))
      (node (ref "J15") (pin "2") (pinfunction "2_2") (pintype "passive"))
      (node (ref "J16") (pin "2") (pinfunction "2_2") (pintype "passive"))
      (node (ref "J17") (pin "2") (pinfunction "2_2") (pintype "passive"))
      (node (ref "J18") (pin "2") (pinfunction "2_2") (pintype "passive"))
      (node (ref "J19") (pin "2") (pinfunction "2_2") (pintype "passive"))
      (node (ref "J2") (pin "2") (pinfunction "2_2") (pintype "passive"))
      (node (ref "J20") (pin "2") (pinfunction "2_2") (pintype "passive"))
      (node (ref "J21") (pin "2") (pinfunction "2_2") (pintype "passive"))
      (node (ref "J22") (pin "2") (pinfunction "2_2") (pintype "passive"))
      (node (ref "J23") (pin "2") (pinfunction "2_2") (pintype "passive"))
      (node (ref "J24") (pin "2") (pinfunction "2_2") (pintype "passive"))
      (node (ref "J25") (pin "2") (pinfunction "2_2") (pintype "passive"))
      (node (ref "J3") (pin "2") (pinfunction "2_2") (pintype "passive"))
      (node (ref "J4") (pin "2") (pinfunction "2_2") (pintype "passive"))
      (node (ref "J5") (pin "2") (pinfunction "2_2") (pintype "passive"))
      (node (ref "J6") (pin "2") (pinfunction "2_2") (pintype "passive"))
      (node (ref "J7") (pin "2") (pinfunction "2_2") (pintype "passive"))
      (node (ref "J8") (pin "2") (pinfunction "2_2") (pintype "passive"))
      (node (ref "J9") (pin "2") (pinfunction "2_2") (pintype "passive"))
      (node (ref "PAD11") (pin "1") (pinfunction "P_1") (pintype "passive"))
      (node (ref "PAD15") (pin "1") (pinfunction "P_1") (pintype "passive"))
      (node (ref "PAD19") (pin "1") (pinfunction "P_1") (pintype "passive"))
      (node (ref "PAD23") (pin "1") (pinfunction "P_1") (pintype "passive"))
      (node (ref "PAD27") (pin "1") (pinfunction "P_1") (pintype "passive"))
      (node (ref "PAD3") (pin "1") (pinfunction "P_1") (pintype "passive"))
      (node (ref "PAD31") (pin "1") (pinfunction "P_1") (pintype "passive"))
      (node (ref "PAD35") (pin "1") (pinfunction "P_1") (pintype "passive"))
      (node (ref "PAD39") (pin "1") (pinfunction "P_1") (pintype "passive"))
      (node (ref "PAD43") (pin "1") (pinfunction "P_1") (pintype "passive"))
      (node (ref "PAD47") (pin "1") (pinfunction "P_1") (pintype "passive"))
      (node (ref "PAD51") (pin "1") (pinfunction "P_1") (pintype "passive"))
      (node (ref "PAD55") (pin "1") (pinfunction "P_1") (pintype "passive"))
      (node (ref "PAD59") (pin "1") (pinfunction "P_1") (pintype "passive"))
      (node (ref "PAD63") (pin "1") (pinfunction "P_1") (pintype "passive"))
      (node (ref "PAD67") (pin "1") (pinfunction "P_1") (pintype "passive"))
      (node (ref "PAD7") (pin "1") (pinfunction "P_1") (pintype "passive"))
      (node (ref "PAD71") (pin "1") (pinfunction "P_1") (pintype "passive"))
      (node (ref "PAD75") (pin "1") (pinfunction "P_1") (pintype "passive"))
      (node (ref "PAD79") (pin "1") (pinfunction "P_1") (pintype "passive"))
      (node (ref "PAD83") (pin "1") (pinfunction "P_1") (pintype "passive"))
      (node (ref "PAD87") (pin "1") (pinfunction "P_1") (pintype "passive"))
      (node (ref "PAD91") (pin "1") (pinfunction "P_1") (pintype "passive"))
      (node (ref "PAD95") (pin "1") (pinfunction "P_1") (pintype "passive"))
      (node (ref "PAD99") (pin "1") (pinfunction "P_1") (pintype "passive"))
    )
    (net (code "12") (name "GPIO1") (class "Default")
      (node (ref "IOEX_RIGHT_1") (pin "2") (pinfunction "2_2") (pintype "passive"))
      (node (ref "J1") (pin "1") (pinfunction "1_1") (pintype "passive"))
    )
    (net (code "13") (name "GPIO2") (class "Default")
      (node (ref "IOEX_RIGHT_1") (pin "3") (pinfunction "3_3") (pintype "passive"))
      (node (ref "J2") (pin "1") (pinfunction "1_1") (pintype "passive"))
    )
    (net (code "14") (name "GPIO3") (class "Default")
      (node (ref "IOEX_RIGHT_1") (pin "4") (pinfunction "4_4") (pintype "passive"))
      (node (ref "J3") (pin "1") (pinfunction "1_1") (pintype "passive"))
    )
    (net (code "15") (name "GPIO4") (class "Default")
      (node (ref "IOEX_RIGHT_1") (pin "5") (pinfunction "5_5") (pintype "passive"))
      (node (ref "J4") (pin "1") (pinfunction "1_1") (pintype "passive"))
    )
    (net (code "16") (name "GPIO5") (class "Default")
      (node (ref "IOEX_RIGHT_1") (pin "6") (pinfunction "6_6") (pintype "passive"))
      (node (ref "J5") (pin "1") (pinfunction "1_1") (pintype "passive"))
    )
    (net (code "17") (name "GPIO6") (class "Default")
      (node (ref "IOEX_RIGHT_1") (pin "7") (pinfunction "7_7") (pintype "passive"))
      (node (ref "J6") (pin "1") (pinfunction "1_1") (pintype "passive"))
    )
    (net (code "18") (name "GPIO7") (class "Default")
      (node (ref "IOEX_RIGHT_1") (pin "8") (pinfunction "8_8") (pintype "passive"))
      (node (ref "J7") (pin "1") (pinfunction "1_1") (pintype "passive"))
    )
    (net (code "19") (name "GPIO8") (class "Default")
      (node (ref "IOEX_RIGHT_1") (pin "9") (pinfunction "9_9") (pintype "passive"))
      (node (ref "J8") (pin "1") (pinfunction "1_1") (pintype "passive"))
    )
    (net (code "20") (name "GPIO9") (class "Default")
      (node (ref "J29") (pin "2") (pinfunction "2_2") (pintype "passive"))
      (node (ref "J9") (pin "1") (pinfunction "1_1") (pintype "passive"))
    )
    (net (code "21") (name "GPIO10") (class "Default")
      (node (ref "J10") (pin "1") (pinfunction "1_1") (pintype "passive"))
      (node (ref "J29") (pin "3") (pinfunction "3_3") (pintype "passive"))
    )
    (net (code "22") (name "GPIO11") (class "Default")
      (node (ref "J11") (pin "1") (pinfunction "1_1") (pintype "passive"))
      (node (ref "J29") (pin "4") (pinfunction "4_4") (pintype "passive"))
    )
    (net (code "23") (name "GPIO12") (class "Default")
      (node (ref "J12") (pin "1") (pinfunction "1_1") (pintype "passive"))
      (node (ref "J29") (pin "5") (pinfunction "5_5") (pintype "passive"))
    )
    (net (code "24") (name "GPIO13") (class "Default")
      (node (ref "J13") (pin "1") (pinfunction "1_1") (pintype "passive"))
      (node (ref "J29") (pin "6") (pinfunction "6_6") (pintype "passive"))
    )
    (net (code "25") (name "GPIO14") (class "Default")
      (node (ref "J14") (pin "1") (pinfunction "1_1") (pintype "passive"))
      (node (ref "J29") (pin "7") (pinfunction "7_7") (pintype "passive"))
    )
    (net (code "26") (name "GPIO15") (class "Default")
      (node (ref "J15") (pin "1") (pinfunction "1_1") (pintype "passive"))
      (node (ref "J29") (pin "8") (pinfunction "8_8") (pintype "passive"))
    )
    (net (code "27") (name "GPIO16") (class "Default")
      (node (ref "J16") (pin "1") (pinfunction "1_1") (pintype "passive"))
      (node (ref "J29") (pin "9") (pinfunction "9_9") (pintype "passive"))
    )
    (net (code "28") (name "GPIO17") (class "Default")
      (node (ref "J17") (pin "1") (pinfunction "1_1") (pintype "passive"))
      (node (ref "J31") (pin "2") (pinfunction "2_2") (pintype "passive"))
    )
    (net (code "29") (name "GPIO18") (class "Default")
      (node (ref "J18") (pin "1") (pinfunction "1_1") (pintype "passive"))
      (node (ref "J31") (pin "3") (pinfunction "3_3") (pintype "passive"))
    )
    (net (code "30") (name "GPIO19") (class "Default")
      (node (ref "J19") (pin "1") (pinfunction "1_1") (pintype "passive"))
      (node (ref "J31") (pin "4") (pinfunction "4_4") (pintype "passive"))
    )
    (net (code "31") (name "GPIO20") (class "Default")
      (node (ref "J20") (pin "1") (pinfunction "1_1") (pintype "passive"))
      (node (ref "J31") (pin "5") (pinfunction "5_5") (pintype "passive"))
    )
    (net (code "32") (name "GPIO21") (class "Default")
      (node (ref "J21") (pin "1") (pinfunction "1_1") (pintype "passive"))
      (node (ref "J31") (pin "6") (pinfunction "6_6") (pintype "passive"))
    )
    (net (code "33") (name "GPIO22") (class "Default")
      (node (ref "J22") (pin "1") (pinfunction "1_1") (pintype "passive"))
      (node (ref "J31") (pin "7") (pinfunction "7_7") (pintype "passive"))
    )
    (net (code "34") (name "GPIO23") (class "Default")
      (node (ref "J23") (pin "1") (pinfunction "1_1") (pintype "passive"))
      (node (ref "J31") (pin "8") (pinfunction "8_8") (pintype "passive"))
    )
    (net (code "35") (name "GPIO24") (class "Default")
      (node (ref "J24") (pin "1") (pinfunction "1_1") (pintype "passive"))
      (node (ref "J31") (pin "9") (pinfunction "9_9") (pintype "passive"))
    )
    (net (code "36") (name "GPIO25") (class "Default")
      (node (ref "J25") (pin "1") (pinfunction "1_1") (pintype "passive"))
    )
    (net (code "37") (name "INT_1") (class "Default")
      (node (ref "IOEX_LEFT_1") (pin "8") (pinfunction "8_8") (pintype "passive"))
    )
    (net (code "38") (name "INT_2") (class "Default")
      (node (ref "J28") (pin "8") (pinfunction "8_8") (pintype "passive"))
    )
    (net (code "39") (name "INT_3") (class "Default")
      (node (ref "J30") (pin "8") (pinfunction "8_8") (pintype "passive"))
    )
    (net (code "40") (name "NC_1") (class "Default")
      (node (ref "IOEX_LEFT_1") (pin "7") (pinfunction "7_7") (pintype "passive"))
    )
    (net (code "41") (name "NC_2") (class "Default")
      (node (ref "J28") (pin "7") (pinfunction "7_7") (pintype "passive"))
    )
    (net (code "42") (name "NC_3") (class "Default")
      (node (ref "J30") (pin "7") (pinfunction "7_7") (pintype "passive"))
    )
    (net (code "43") (name "RESET_1") (class "Default")
      (node (ref "IOEX_LEFT_1") (pin "6") (pinfunction "6_6") (pintype "passive"))
    )
    (net (code "44") (name "RESET_2") (class "Default")
      (node (ref "J28") (pin "6") (pinfunction "6_6") (pintype "passive"))
    )
    (net (code "45") (name "RESET_3") (class "Default")
      (node (ref "J30") (pin "6") (pinfunction "6_6") (pintype "passive"))
    )
    (net (code "46") (name "SCL") (class "Default")
      (node (ref "IOEX_LEFT_1") (pin "1") (pinfunction "1_1") (pintype "passive"))
      (node (ref "J28") (pin "1") (pinfunction "1_1") (pintype "passive"))
      (node (ref "J30") (pin "1") (pinfunction "1_1") (pintype "passive"))
      (node (ref "PAD10") (pin "1") (pinfunction "P_1") (pintype "passive"))
      (node (ref "PAD14") (pin "1") (pinfunction "P_1") (pintype "passive"))
      (node (ref "PAD18") (pin "1") (pinfunction "P_1") (pintype "passive"))
      (node (ref "PAD2") (pin "1") (pinfunction "P_1") (pintype "passive"))
      (node (ref "PAD22") (pin "1") (pinfunction "P_1") (pintype "passive"))
      (node (ref "PAD26") (pin "1") (pinfunction "P_1") (pintype "passive"))
      (node (ref "PAD30") (pin "1") (pinfunction "P_1") (pintype "passive"))
      (node (ref "PAD34") (pin "1") (pinfunction "P_1") (pintype "passive"))
      (node (ref "PAD38") (pin "1") (pinfunction "P_1") (pintype "passive"))
      (node (ref "PAD42") (pin "1") (pinfunction "P_1") (pintype "passive"))
      (node (ref "PAD46") (pin "1") (pinfunction "P_1") (pintype "passive"))
      (node (ref "PAD50") (pin "1") (pinfunction "P_1") (pintype "passive"))
      (node (ref "PAD54") (pin "1") (pinfunction "P_1") (pintype "passive"))
      (node (ref "PAD58") (pin "1") (pinfunction "P_1") (pintype "passive"))
      (node (ref "PAD6") (pin "1") (pinfunction "P_1") (pintype "passive"))
      (node (ref "PAD62") (pin "1") (pinfunction "P_1") (pintype "passive"))
      (node (ref "PAD66") (pin "1") (pinfunction "P_1") (pintype "passive"))
      (node (ref "PAD70") (pin "1") (pinfunction "P_1") (pintype "passive"))
      (node (ref "PAD74") (pin "1") (pinfunction "P_1") (pintype "passive"))
      (node (ref "PAD78") (pin "1") (pinfunction "P_1") (pintype "passive"))
      (node (ref "PAD82") (pin "1") (pinfunction "P_1") (pintype "passive"))
      (node (ref "PAD86") (pin "1") (pinfunction "P_1") (pintype "passive"))
      (node (ref "PAD90") (pin "1") (pinfunction "P_1") (pintype "passive"))
      (node (ref "PAD94") (pin "1") (pinfunction "P_1") (pintype "passive"))
      (node (ref "PAD98") (pin "1") (pinfunction "P_1") (pintype "passive"))
      (node (ref "SCL") (pin "1") (pinfunction "P_1") (pintype "passive"))
      (node (ref "SCL1") (pin "1") (pinfunction "P_1") (pintype "passive"))
      (node (ref "SCL10") (pin "1") (pinfunction "P_1") (pintype "passive"))
      (node (ref "SCL11") (pin "1") (pinfunction "P_1") (pintype "passive"))
      (node (ref "SCL12") (pin "1") (pinfunction "P_1") (pintype "passive"))
      (node (ref "SCL13") (pin "1") (pinfunction "P_1") (pintype "passive"))
      (node (ref "SCL14") (pin "1") (pinfunction "P_1") (pintype "passive"))
      (node (ref "SCL15") (pin "1") (pinfunction "P_1") (pintype "passive"))
      (node (ref "SCL16") (pin "1") (pinfunction "P_1") (pintype "passive"))
      (node (ref "SCL17") (pin "1") (pinfunction "P_1") (pintype "passive"))
      (node (ref "SCL18") (pin "1") (pinfunction "P_1") (pintype "passive"))
      (node (ref "SCL19") (pin "1") (pinfunction "P_1") (pintype "passive"))
      (node (ref "SCL2") (pin "1") (pinfunction "P_1") (pintype "passive"))
      (node (ref "SCL20") (pin "1") (pinfunction "P_1") (pintype "passive"))
      (node (ref "SCL21") (pin "1") (pinfunction "P_1") (pintype "passive"))
      (node (ref "SCL22") (pin "1") (pinfunction "P_1") (pintype "passive"))
      (node (ref "SCL23") (pin "1") (pinfunction "P_1") (pintype "passive"))
      (node (ref "SCL24") (pin "1") (pinfunction "P_1") (pintype "passive"))
      (node (ref "SCL3") (pin "1") (pinfunction "P_1") (pintype "passive"))
      (node (ref "SCL4") (pin "1") (pinfunction "P_1") (pintype "passive"))
      (node (ref "SCL5") (pin "1") (pinfunction "P_1") (pintype "passive"))
      (node (ref "SCL6") (pin "1") (pinfunction "P_1") (pintype "passive"))
      (node (ref "SCL7") (pin "1") (pinfunction "P_1") (pintype "passive"))
      (node (ref "SCL8") (pin "1") (pinfunction "P_1") (pintype "passive"))
      (node (ref "SCL9") (pin "1") (pinfunction "P_1") (pintype "passive"))
    )
    (net (code "47") (name "SDA") (class "Default")
      (node (ref "IOEX_LEFT_1") (pin "2") (pinfunction "2_2") (pintype "passive"))
      (node (ref "J28") (pin "2") (pinfunction "2_2") (pintype "passive"))
      (node (ref "J30") (pin "2") (pinfunction "2_2") (pintype "passive"))
      (node (ref "PAD100") (pin "1") (pinfunction "P_1") (pintype "passive"))
      (node (ref "PAD12") (pin "1") (pinfunction "P_1") (pintype "passive"))
      (node (ref "PAD16") (pin "1") (pinfunction "P_1") (pintype "passive"))
      (node (ref "PAD20") (pin "1") (pinfunction "P_1") (pintype "passive"))
      (node (ref "PAD24") (pin "1") (pinfunction "P_1") (pintype "passive"))
      (node (ref "PAD28") (pin "1") (pinfunction "P_1") (pintype "passive"))
      (node (ref "PAD32") (pin "1") (pinfunction "P_1") (pintype "passive"))
      (node (ref "PAD36") (pin "1") (pinfunction "P_1") (pintype "passive"))
      (node (ref "PAD4") (pin "1") (pinfunction "P_1") (pintype "passive"))
      (node (ref "PAD40") (pin "1") (pinfunction "P_1") (pintype "passive"))
      (node (ref "PAD44") (pin "1") (pinfunction "P_1") (pintype "passive"))
      (node (ref "PAD48") (pin "1") (pinfunction "P_1") (pintype "passive"))
      (node (ref "PAD52") (pin "1") (pinfunction "P_1") (pintype "passive"))
      (node (ref "PAD56") (pin "1") (pinfunction "P_1") (pintype "passive"))
      (node (ref "PAD60") (pin "1") (pinfunction "P_1") (pintype "passive"))
      (node (ref "PAD64") (pin "1") (pinfunction "P_1") (pintype "passive"))
      (node (ref "PAD68") (pin "1") (pinfunction "P_1") (pintype "passive"))
      (node (ref "PAD72") (pin "1") (pinfunction "P_1") (pintype "passive"))
      (node (ref "PAD76") (pin "1") (pinfunction "P_1") (pintype "passive"))
      (node (ref "PAD8") (pin "1") (pinfunction "P_1") (pintype "passive"))
      (node (ref "PAD80") (pin "1") (pinfunction "P_1") (pintype "passive"))
      (node (ref "PAD84") (pin "1") (pinfunction "P_1") (pintype "passive"))
      (node (ref "PAD88") (pin "1") (pinfunction "P_1") (pintype "passive"))
      (node (ref "PAD92") (pin "1") (pinfunction "P_1") (pintype "passive"))
      (node (ref "PAD96") (pin "1") (pinfunction "P_1") (pintype "passive"))
      (node (ref "SDA") (pin "1") (pinfunction "P_1") (pintype "passive"))
      (node (ref "SDA1") (pin "1") (pinfunction "P_1") (pintype "passive"))
      (node (ref "SDA10") (pin "1") (pinfunction "P_1") (pintype "passive"))
      (node (ref "SDA11") (pin "1") (pinfunction "P_1") (pintype "passive"))
      (node (ref "SDA12") (pin "1") (pinfunction "P_1") (pintype "passive"))
      (node (ref "SDA13") (pin "1") (pinfunction "P_1") (pintype "passive"))
      (node (ref "SDA14") (pin "1") (pinfunction "P_1") (pintype "passive"))
      (node (ref "SDA15") (pin "1") (pinfunction "P_1") (pintype "passive"))
      (node (ref "SDA16") (pin "1") (pinfunction "P_1") (pintype "passive"))
      (node (ref "SDA17") (pin "1") (pinfunction "P_1") (pintype "passive"))
      (node (ref "SDA18") (pin "1") (pinfunction "P_1") (pintype "passive"))
      (node (ref "SDA19") (pin "1") (pinfunction "P_1") (pintype "passive"))
      (node (ref "SDA2") (pin "1") (pinfunction "P_1") (pintype "passive"))
      (node (ref "SDA20") (pin "1") (pinfunction "P_1") (pintype "passive"))
      (node (ref "SDA21") (pin "1") (pinfunction "P_1") (pintype "passive"))
      (node (ref "SDA22") (pin "1") (pinfunction "P_1") (pintype "passive"))
      (node (ref "SDA23") (pin "1") (pinfunction "P_1") (pintype "passive"))
      (node (ref "SDA24") (pin "1") (pinfunction "P_1") (pintype "passive"))
      (node (ref "SDA3") (pin "1") (pinfunction "P_1") (pintype "passive"))
      (node (ref "SDA4") (pin "1") (pinfunction "P_1") (pintype "passive"))
      (node (ref "SDA5") (pin "1") (pinfunction "P_1") (pintype "passive"))
      (node (ref "SDA6") (pin "1") (pinfunction "P_1") (pintype "passive"))
      (node (ref "SDA7") (pin "1") (pinfunction "P_1") (pintype "passive"))
      (node (ref "SDA8") (pin "1") (pinfunction "P_1") (pintype "passive"))
      (node (ref "SDA9") (pin "1") (pinfunction "P_1") (pintype "passive"))
    )
    (net (code "48") (name "VCC") (class "Default")
      (node (ref "J10") (pin "3") (pinfunction "3_3") (pintype "passive"))
      (node (ref "J11") (pin "3") (pinfunction "3_3") (pintype "passive"))
      (node (ref "J12") (pin "3") (pinfunction "3_3") (pintype "passive"))
      (node (ref "J13") (pin "3") (pinfunction "3_3") (pintype "passive"))
      (node (ref "J14") (pin "3") (pinfunction "3_3") (pintype "passive"))
      (node (ref "J15") (pin "3") (pinfunction "3_3") (pintype "passive"))
      (node (ref "J16") (pin "3") (pinfunction "3_3") (pintype "passive"))
      (node (ref "J17") (pin "3") (pinfunction "3_3") (pintype "passive"))
      (node (ref "J18") (pin "3") (pinfunction "3_3") (pintype "passive"))
      (node (ref "J19") (pin "3") (pinfunction "3_3") (pintype "passive"))
      (node (ref "J2") (pin "3") (pinfunction "3_3") (pintype "passive"))
      (node (ref "J20") (pin "3") (pinfunction "3_3") (pintype "passive"))
      (node (ref "J21") (pin "3") (pinfunction "3_3") (pintype "passive"))
      (node (ref "J22") (pin "3") (pinfunction "3_3") (pintype "passive"))
      (node (ref "J23") (pin "3") (pinfunction "3_3") (pintype "passive"))
      (node (ref "J24") (pin "3") (pinfunction "3_3") (pintype "passive"))
      (node (ref "J25") (pin "3") (pinfunction "3_3") (pintype "passive"))
      (node (ref "J3") (pin "3") (pinfunction "3_3") (pintype "passive"))
      (node (ref "J4") (pin "3") (pinfunction "3_3") (pintype "passive"))
      (node (ref "J5") (pin "3") (pinfunction "3_3") (pintype "passive"))
      (node (ref "J6") (pin "3") (pinfunction "3_3") (pintype "passive"))
      (node (ref "J7") (pin "3") (pinfunction "3_3") (pintype "passive"))
      (node (ref "J8") (pin "3") (pinfunction "3_3") (pintype "passive"))
      (node (ref "J9") (pin "3") (pinfunction "3_3") (pintype "passive"))
      (node (ref "PAD1") (pin "1") (pinfunction "P_1") (pintype "passive"))
      (node (ref "PAD13") (pin "1") (pinfunction "P_1") (pintype "passive"))
      (node (ref "PAD17") (pin "1") (pinfunction "P_1") (pintype "passive"))
      (node (ref "PAD21") (pin "1") (pinfunction "P_1") (pintype "passive"))
      (node (ref "PAD25") (pin "1") (pinfunction "P_1") (pintype "passive"))
      (node (ref "PAD29") (pin "1") (pinfunction "P_1") (pintype "passive"))
      (node (ref "PAD33") (pin "1") (pinfunction "P_1") (pintype "passive"))
      (node (ref "PAD37") (pin "1") (pinfunction "P_1") (pintype "passive"))
      (node (ref "PAD41") (pin "1") (pinfunction "P_1") (pintype "passive"))
      (node (ref "PAD45") (pin "1") (pinfunction "P_1") (pintype "passive"))
      (node (ref "PAD49") (pin "1") (pinfunction "P_1") (pintype "passive"))
      (node (ref "PAD5") (pin "1") (pinfunction "P_1") (pintype "passive"))
      (node (ref "PAD53") (pin "1") (pinfunction "P_1") (pintype "passive"))
      (node (ref "PAD57") (pin "1") (pinfunction "P_1") (pintype "passive"))
      (node (ref "PAD61") (pin "1") (pinfunction "P_1") (pintype "passive"))
      (node (ref "PAD65") (pin "1") (pinfunction "P_1") (pintype "passive"))
      (node (ref "PAD69") (pin "1") (pinfunction "P_1") (pintype "passive"))
      (node (ref "PAD73") (pin "1") (pinfunction "P_1") (pintype "passive"))
      (node (ref "PAD77") (pin "1") (pinfunction "P_1") (pintype "passive"))
      (node (ref "PAD81") (pin "1") (pinfunction "P_1") (pintype "passive"))
      (node (ref "PAD85") (pin "1") (pinfunction "P_1") (pintype "passive"))
      (node (ref "PAD89") (pin "1") (pinfunction "P_1") (pintype "passive"))
      (node (ref "PAD9") (pin "1") (pinfunction "P_1") (pintype "passive"))
      (node (ref "PAD93") (pin "1") (pinfunction "P_1") (pintype "passive"))
      (node (ref "PAD97") (pin "1") (pinfunction "P_1") (pintype "passive"))
      (node (ref "VCC") (pin "1") (pinfunction "P_1") (pintype "passive"))
      (node (ref "VCC1") (pin "1") (pinfunction "P_1") (pintype "passive"))
      (node (ref "VCC10") (pin "1") (pinfunction "P_1") (pintype "passive"))
      (node (ref "VCC11") (pin "1") (pinfunction "P_1") (pintype "passive"))
      (node (ref "VCC12") (pin "1") (pinfunction "P_1") (pintype "passive"))
      (node (ref "VCC13") (pin "1") (pinfunction "P_1") (pintype "passive"))
      (node (ref "VCC14") (pin "1") (pinfunction "P_1") (pintype "passive"))
      (node (ref "VCC15") (pin "1") (pinfunction "P_1") (pintype "passive"))
      (node (ref "VCC16") (pin "1") (pinfunction "P_1") (pintype "passive"))
      (node (ref "VCC17") (pin "1") (pinfunction "P_1") (pintype "passive"))
      (node (ref "VCC18") (pin "1") (pinfunction "P_1") (pintype "passive"))
      (node (ref "VCC19") (pin "1") (pinfunction "P_1") (pintype "passive"))
      (node (ref "VCC2") (pin "1") (pinfunction "P_1") (pintype "passive"))
      (node (ref "VCC20") (pin "1") (pinfunction "P_1") (pintype "passive"))
      (node (ref "VCC21") (pin "1") (pinfunction "P_1") (pintype "passive"))
      (node (ref "VCC22") (pin "1") (pinfunction "P_1") (pintype "passive"))
      (node (ref "VCC23") (pin "1") (pinfunction "P_1") (pintype "passive"))
      (node (ref "VCC24") (pin "1") (pinfunction "P_1") (pintype "passive"))
      (node (ref "VCC3") (pin "1") (pinfunction "P_1") (pintype "passive"))
      (node (ref "VCC4") (pin "1") (pinfunction "P_1") (pintype "passive"))
      (node (ref "VCC5") (pin "1") (pinfunction "P_1") (pintype "passive"))
      (node (ref "VCC6") (pin "1") (pinfunction "P_1") (pintype "passive"))
      (node (ref "VCC7") (pin "1") (pinfunction "P_1") (pintype "passive"))
      (node (ref "VCC8") (pin "1") (pinfunction "P_1") (pintype "passive"))
      (node (ref "VCC9") (pin "1") (pinfunction "P_1") (pintype "passive"))
    )
    (net (code "49") (name "VDD_1") (class "Default")
      (node (ref "IOEX_RIGHT_1") (pin "1") (pinfunction "1_1") (pintype "passive"))
    )
    (net (code "50") (name "VDD_2") (class "Default")
      (node (ref "J29") (pin "1") (pinfunction "1_1") (pintype "passive"))
    )
    (net (code "51") (name "VDD_3") (class "Default")
      (node (ref "J31") (pin "1") (pinfunction "1_1") (pintype "passive"))
    )
    (net (code "52") (name "VSS_1") (class "Default")
      (node (ref "IOEX_LEFT_1") (pin "9") (pinfunction "9_9") (pintype "passive"))
    )
    (net (code "53") (name "VSS_2") (class "Default")
      (node (ref "J28") (pin "9") (pinfunction "9_9") (pintype "passive"))
    )
    (net (code "54") (name "VSS_3") (class "Default")
      (node (ref "J30") (pin "9") (pinfunction "9_9") (pintype "passive"))
    )
    (net (code "55") (name "unconnected-(J32-Pad1)") (class "Default")
      (node (ref "J32") (pin "1") (pinfunction "1_1") (pintype "passive"))
    )
    (net (code "56") (name "unconnected-(J32-Pad2)") (class "Default")
      (node (ref "J32") (pin "2") (pinfunction "2_2") (pintype "passive"))
    )
    (net (code "57") (name "unconnected-(J32-Pad3)") (class "Default")
      (node (ref "J32") (pin "3") (pinfunction "3_3") (pintype "passive"))
    )
    (net (code "58") (name "unconnected-(J32-Pad4)") (class "Default")
      (node (ref "J32") (pin "4") (pinfunction "4_4") (pintype "passive"))
    )
    (net (code "59") (name "unconnected-(J32-Pad5)") (class "Default")
      (node (ref "J32") (pin "5") (pinfunction "5_5") (pintype "passive"))
    )
    (net (code "60") (name "unconnected-(J32-Pad6)") (class "Default")
      (node (ref "J32") (pin "6") (pinfunction "6_6") (pintype "passive"))
    )
    (net (code "61") (name "unconnected-(J32-Pad7)") (class "Default")
      (node (ref "J32") (pin "7") (pinfunction "7_7") (pintype "passive"))
    )
    (net (code "62") (name "unconnected-(J32-Pad8)") (class "Default")
      (node (ref "J32") (pin "8") (pinfunction "8_8") (pintype "passive"))
    )
    (net (code "63") (name "unconnected-(J32-Pad9)") (class "Default")
      (node (ref "J32") (pin "9") (pinfunction "9_9") (pintype "passive"))
    )
    (net (code "64") (name "unconnected-(J32-Pad10)") (class "Default")
      (node (ref "J32") (pin "10") (pinfunction "10_10") (pintype "passive"))
    )
    (net (code "65") (name "unconnected-(J32-Pad11)") (class "Default")
      (node (ref "J32") (pin "11") (pinfunction "11_11") (pintype "passive"))
    )
    (net (code "66") (name "unconnected-(J32-Pad12)") (class "Default")
      (node (ref "J32") (pin "12") (pinfunction "12_12") (pintype "passive"))
    )
    (net (code "67") (name "unconnected-(J32-Pad13)") (class "Default")
      (node (ref "J32") (pin "13") (pinfunction "13_13") (pintype "passive"))
    )
    (net (code "68") (name "unconnected-(J32-Pad14)") (class "Default")
      (node (ref "J32") (pin "14") (pinfunction "14_14") (pintype "passive"))
    )
    (net (code "69") (name "unconnected-(J32-Pad15)") (class "Default")
      (node (ref "J32") (pin "15") (pinfunction "15_15") (pintype "passive"))
    )
    (net (code "70") (name "unconnected-(J33-Pad1)") (class "Default")
      (node (ref "J33") (pin "1") (pinfunction "1_1") (pintype "passive"))
    )
    (net (code "71") (name "unconnected-(J33-Pad2)") (class "Default")
      (node (ref "J33") (pin "2") (pinfunction "2_2") (pintype "passive"))
    )
    (net (code "72") (name "unconnected-(J33-Pad3)") (class "Default")
      (node (ref "J33") (pin "3") (pinfunction "3_3") (pintype "passive"))
    )
    (net (code "73") (name "unconnected-(J33-Pad4)") (class "Default")
      (node (ref "J33") (pin "4") (pinfunction "4_4") (pintype "passive"))
    )
    (net (code "74") (name "unconnected-(J33-Pad5)") (class "Default")
      (node (ref "J33") (pin "5") (pinfunction "5_5") (pintype "passive"))
    )
    (net (code "75") (name "unconnected-(J33-Pad6)") (class "Default")
      (node (ref "J33") (pin "6") (pinfunction "6_6") (pintype "passive"))
    )
    (net (code "76") (name "unconnected-(J33-Pad7)") (class "Default")
      (node (ref "J33") (pin "7") (pinfunction "7_7") (pintype "passive"))
    )
    (net (code "77") (name "unconnected-(J33-Pad8)") (class "Default")
      (node (ref "J33") (pin "8") (pinfunction "8_8") (pintype "passive"))
    )
    (net (code "78") (name "unconnected-(J33-Pad9)") (class "Default")
      (node (ref "J33") (pin "9") (pinfunction "9_9") (pintype "passive"))
    )
    (net (code "79") (name "unconnected-(J33-Pad10)") (class "Default")
      (node (ref "J33") (pin "10") (pinfunction "10_10") (pintype "passive"))
    )
    (net (code "80") (name "unconnected-(J33-Pad11)") (class "Default")
      (node (ref "J33") (pin "11") (pinfunction "11_11") (pintype "passive"))
    )
    (net (code "81") (name "unconnected-(J33-Pad12)") (class "Default")
      (node (ref "J33") (pin "12") (pinfunction "12_12") (pintype "passive"))
    )
    (net (code "82") (name "unconnected-(J33-Pad13)") (class "Default")
      (node (ref "J33") (pin "13") (pinfunction "13_13") (pintype "passive"))
    )
    (net (code "83") (name "unconnected-(J33-Pad14)") (class "Default")
      (node (ref "J33") (pin "14") (pinfunction "14_14") (pintype "passive"))
    )
    (net (code "84") (name "unconnected-(J33-Pad15)") (class "Default")
      (node (ref "J33") (pin "15") (pinfunction "15_15") (pintype "passive"))
    )
  )
)
